# ups_unit.net
KiCad netlist of a schematic drawn in EAGLE
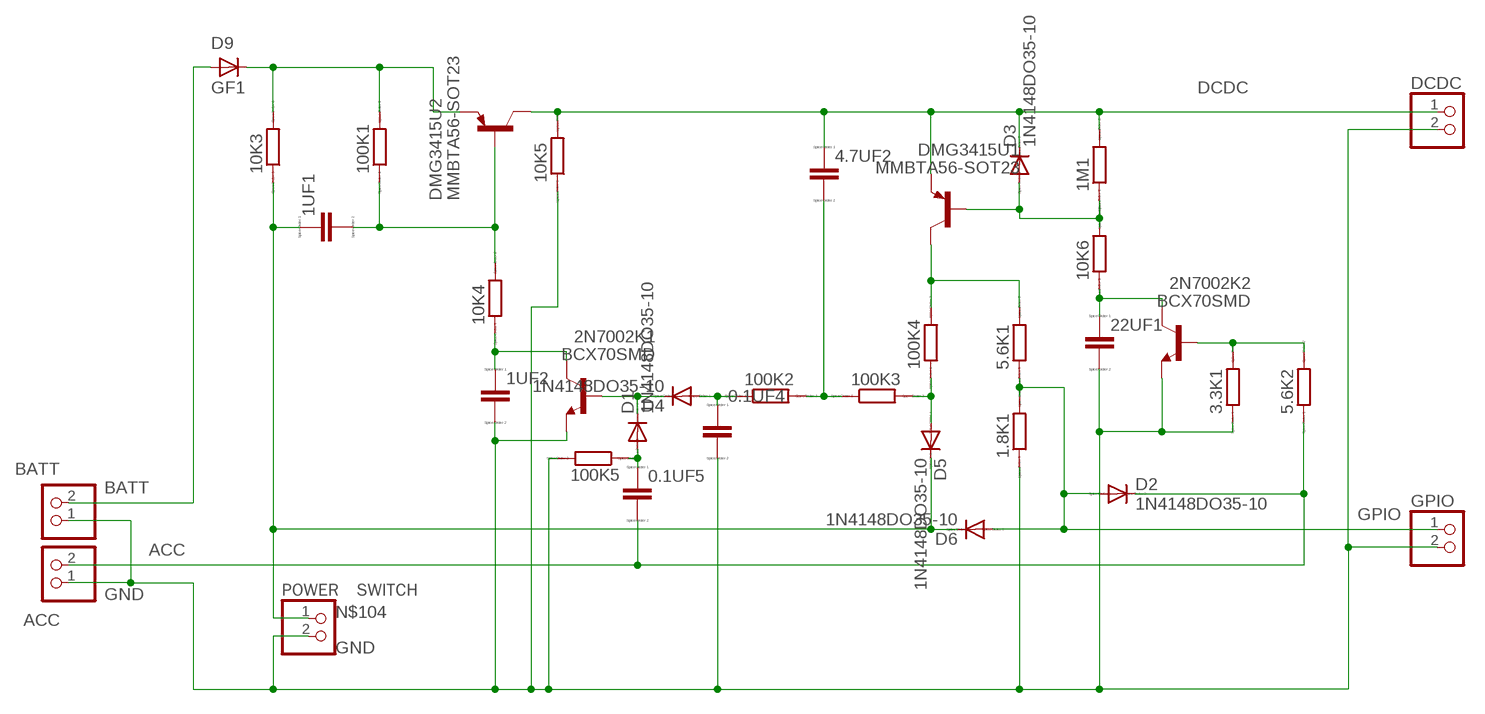
[diagram p0: schematic, sheet 1]

(export (version "E")
  (design (tool "Eeschema 10.0.6"))
  (components
    (comp (ref "0.1UF4")
      (value "CC1206")
      (footprint "eagle-import:C1206")
      (libsource (lib "eagle-import") (part "CC1206"))
    )
    (comp (ref "0.1UF5")
      (value "CC1206")
      (footprint "eagle-import:C1206")
      (libsource (lib "eagle-import") (part "CC1206"))
    )
    (comp (ref "1.8K1")
      (value "RR1206")
      (footprint "eagle-import:R1206")
      (libsource (lib "eagle-import") (part "RR1206"))
    )
    (comp (ref "1M1")
      (value "RR1206")
      (footprint "eagle-import:R1206")
      (libsource (lib "eagle-import") (part "RR1206"))
    )
    (comp (ref "1UF1")
      (value "CC0603")
      (footprint "eagle-import:C0603")
      (libsource (lib "eagle-import") (part "CC0603"))
    )
    (comp (ref "1UF2")
      (value "CC0603")
      (footprint "eagle-import:C0603")
      (libsource (lib "eagle-import") (part "CC0603"))
    )
    (comp (ref "2N7002K1")
      (value "BCX70SMD")
      (footprint "eagle-import:SOT23")
      (libsource (lib "eagle-import") (part "BCX70SMD"))
    )
    (comp (ref "2N7002K2")
      (value "BCX70SMD")
      (footprint "eagle-import:SOT23")
      (libsource (lib "eagle-import") (part "BCX70SMD"))
    )
    (comp (ref "3.3K1")
      (value "RR1206")
      (footprint "eagle-import:R1206")
      (libsource (lib "eagle-import") (part "RR1206"))
    )
    (comp (ref "4.7UF2")
      (value "CC2012")
      (footprint "eagle-import:C2012")
      (libsource (lib "eagle-import") (part "CC2012"))
    )
    (comp (ref "5.6K1")
      (value "RR1206")
      (footprint "eagle-import:R1206")
      (libsource (lib "eagle-import") (part "RR1206"))
    )
    (comp (ref "5.6K2")
      (value "RR1206")
      (footprint "eagle-import:R1206")
      (libsource (lib "eagle-import") (part "RR1206"))
    )
    (comp (ref "10K3")
      (value "RR1206")
      (footprint "eagle-import:R1206")
      (libsource (lib "eagle-import") (part "RR1206"))
    )
    (comp (ref "10K4")
      (value "RR1206")
      (footprint "eagle-import:R1206")
      (libsource (lib "eagle-import") (part "RR1206"))
    )
    (comp (ref "10K5")
      (value "RR1206")
      (footprint "eagle-import:R1206")
      (libsource (lib "eagle-import") (part "RR1206"))
    )
    (comp (ref "10K6")
      (value "RR1206")
      (footprint "eagle-import:R1206")
      (libsource (lib "eagle-import") (part "RR1206"))
    )
    (comp (ref "22UF1")
      (value "C")
      (footprint "eagle-import:C0805")
      (libsource (lib "eagle-import") (part "C"))
    )
    (comp (ref "100K1")
      (value "RR1206")
      (footprint "eagle-import:R1206")
      (libsource (lib "eagle-import") (part "RR1206"))
    )
    (comp (ref "100K2")
      (value "RR1206")
      (footprint "eagle-import:R1206")
      (libsource (lib "eagle-import") (part "RR1206"))
    )
    (comp (ref "100K3")
      (value "RR1206")
      (footprint "eagle-import:R1206")
      (libsource (lib "eagle-import") (part "RR1206"))
    )
    (comp (ref "100K4")
      (value "RR1206")
      (footprint "eagle-import:R1206")
      (libsource (lib "eagle-import") (part "RR1206"))
    )
    (comp (ref "100K5")
      (value "RR1206")
      (footprint "eagle-import:R1206")
      (libsource (lib "eagle-import") (part "RR1206"))
    )
    (comp (ref "ACC")
      (value "PINHD-1X2")
      (footprint "eagle-import:1X02")
      (libsource (lib "eagle-import") (part "PINHD-1X2"))
    )
    (comp (ref "BATT")
      (value "PINHD-1X2")
      (footprint "eagle-import:1X02")
      (libsource (lib "eagle-import") (part "PINHD-1X2"))
    )
    (comp (ref "D1")
      (value "1N4148DO35-10")
      (footprint "eagle-import:DO35-10")
      (libsource (lib "eagle-import") (part "1N4148DO35-10"))
    )
    (comp (ref "D2")
      (value "1N4148DO35-10")
      (footprint "eagle-import:DO35-10")
      (libsource (lib "eagle-import") (part "1N4148DO35-10"))
    )
    (comp (ref "D3")
      (value "1N4148DO35-10")
      (footprint "eagle-import:DO35-10")
      (libsource (lib "eagle-import") (part "1N4148DO35-10"))
    )
    (comp (ref "D4")
      (value "1N4148DO35-10")
      (footprint "eagle-import:DO35-10")
      (libsource (lib "eagle-import") (part "1N4148DO35-10"))
    )
    (comp (ref "D5")
      (value "1N4148DO35-10")
      (footprint "eagle-import:DO35-10")
      (libsource (lib "eagle-import") (part "1N4148DO35-10"))
    )
    (comp (ref "D6")
      (value "1N4148DO35-10")
      (footprint "eagle-import:DO35-10")
      (libsource (lib "eagle-import") (part "1N4148DO35-10"))
    )
    (comp (ref "D9")
      (value "GF1")
      (footprint "eagle-import:SMA-DO214AC")
      (libsource (lib "eagle-import") (part "GF1"))
    )
    (comp (ref "DCDC")
      (value "PINHD-1X2")
      (footprint "eagle-import:1X02")
      (libsource (lib "eagle-import") (part "PINHD-1X2"))
    )
    (comp (ref "DMG3415U1")
      (value "MMBTA56-SOT23")
      (footprint "eagle-import:SOT23")
      (libsource (lib "eagle-import") (part "-?SOT23MMBTA56"))
    )
    (comp (ref "DMG3415U2")
      (value "MMBTA56-SOT23")
      (footprint "eagle-import:SOT23")
      (libsource (lib "eagle-import") (part "-?SOT23MMBTA56"))
    )
    (comp (ref "GPIO")
      (value "PINHD-1X2")
      (footprint "eagle-import:1X02")
      (libsource (lib "eagle-import") (part "PINHD-1X2"))
    )
    (comp (ref "POWER　SWITCH")
      (value "PINHD-1X2")
      (footprint "eagle-import:1X02")
      (libsource (lib "eagle-import") (part "PINHD-1X2"))
    )
  )
  (nets
    (net (code "1") (name "/ACC") (class "Default")
      (node (ref "0.1UF5") (pin "2") (pinfunction "2_2") (pintype "passive"))
      (node (ref "5.6K2") (pin "1") (pinfunction "1_1") (pintype "passive"))
      (node (ref "ACC") (pin "2") (pinfunction "2_2") (pintype "passive"))
      (node (ref "D2") (pin "C") (pinfunction "C_C") (pintype "passive"))
    )
    (net (code "2") (name "/BATT") (class "Default")
      (node (ref "BATT") (pin "2") (pinfunction "2_2") (pintype "passive"))
      (node (ref "D9") (pin "A") (pinfunction "A_A") (pintype "passive"))
    )
    (net (code "3") (name "/DCDC") (class "Default")
      (node (ref "10K5") (pin "2") (pinfunction "2_2") (pintype "passive"))
      (node (ref "1M1") (pin "2") (pinfunction "2_2") (pintype "passive"))
      (node (ref "4.7UF2") (pin "1") (pinfunction "1_1") (pintype "passive"))
      (node (ref "D3") (pin "C") (pinfunction "C_C") (pintype "passive"))
      (node (ref "DCDC") (pin "1") (pinfunction "1_1") (pintype "passive"))
      (node (ref "DMG3415U1") (pin "2") (pinfunction "E_2") (pintype "passive"))
      (node (ref "DMG3415U2") (pin "3") (pinfunction "C_3") (pintype "passive"))
    )
    (net (code "4") (name "/GND") (class "Default")
      (node (ref "0.1UF4") (pin "2") (pinfunction "2_2") (pintype "passive"))
      (node (ref "1.8K1") (pin "1") (pinfunction "1_1") (pintype "passive"))
      (node (ref "100K5") (pin "2") (pinfunction "2_2") (pintype "passive"))
      (node (ref "10K5") (pin "1") (pinfunction "1_1") (pintype "passive"))
      (node (ref "1UF2") (pin "2") (pinfunction "2_2") (pintype "passive"))
      (node (ref "22UF1") (pin "2") (pinfunction "2_2") (pintype "passive"))
      (node (ref "2N7002K1") (pin "2") (pinfunction "E_2") (pintype "passive"))
      (node (ref "2N7002K2") (pin "2") (pinfunction "E_2") (pintype "passive"))
      (node (ref "3.3K1") (pin "1") (pinfunction "1_1") (pintype "passive"))
      (node (ref "ACC") (pin "1") (pinfunction "1_1") (pintype "passive"))
      (node (ref "BATT") (pin "1") (pinfunction "1_1") (pintype "passive"))
      (node (ref "DCDC") (pin "2") (pinfunction "2_2") (pintype "passive"))
      (node (ref "GPIO") (pin "2") (pinfunction "2_2") (pintype "passive"))
      (node (ref "POWER　SWITCH") (pin "2") (pinfunction "2_2") (pintype "passive"))
    )
    (net (code "5") (name "/GPIO") (class "Default")
      (node (ref "1.8K1") (pin "2") (pinfunction "2_2") (pintype "passive"))
      (node (ref "5.6K1") (pin "1") (pinfunction "1_1") (pintype "passive"))
      (node (ref "D2") (pin "A") (pinfunction "A_A") (pintype "passive"))
      (node (ref "D6") (pin "A") (pinfunction "A_A") (pintype "passive"))
      (node (ref "GPIO") (pin "1") (pinfunction "1_1") (pintype "passive"))
    )
    (net (code "6") (name "/N$104") (class "Default")
      (node (ref "10K3") (pin "1") (pinfunction "1_1") (pintype "passive"))
      (node (ref "1UF1") (pin "1") (pinfunction "1_1") (pintype "passive"))
      (node (ref "D5") (pin "C") (pinfunction "C_C") (pintype "passive"))
      (node (ref "D6") (pin "C") (pinfunction "C_C") (pintype "passive"))
      (node (ref "POWER　SWITCH") (pin "1") (pinfunction "1_1") (pintype "passive"))
    )
    (net (code "7") (name "Net-(0.1UF4-Pad1)") (class "Default")
      (node (ref "0.1UF4") (pin "1") (pinfunction "1_1") (pintype "passive"))
      (node (ref "100K2") (pin "1") (pinfunction "1_1") (pintype "passive"))
      (node (ref "D4") (pin "A") (pinfunction "A_A") (pintype "passive"))
    )
    (net (code "8") (name "Net-(0.1UF5-Pad1)") (class "Default")
      (node (ref "0.1UF5") (pin "1") (pinfunction "1_1") (pintype "passive"))
      (node (ref "100K5") (pin "1") (pinfunction "1_1") (pintype "passive"))
      (node (ref "D1") (pin "A") (pinfunction "A_A") (pintype "passive"))
    )
    (net (code "9") (name "Net-(2N7002K1-B)") (class "Default")
      (node (ref "2N7002K1") (pin "1") (pinfunction "B_1") (pintype "passive"))
      (node (ref "D1") (pin "C") (pinfunction "C_C") (pintype "passive"))
      (node (ref "D4") (pin "C") (pinfunction "C_C") (pintype "passive"))
    )
    (net (code "10") (name "Net-(2N7002K1-C)") (class "Default")
      (node (ref "10K4") (pin "1") (pinfunction "1_1") (pintype "passive"))
      (node (ref "1UF2") (pin "1") (pinfunction "1_1") (pintype "passive"))
      (node (ref "2N7002K1") (pin "3") (pinfunction "C_3") (pintype "passive"))
    )
    (net (code "11") (name "Net-(2N7002K2-B)") (class "Default")
      (node (ref "2N7002K2") (pin "1") (pinfunction "B_1") (pintype "passive"))
      (node (ref "3.3K1") (pin "2") (pinfunction "2_2") (pintype "passive"))
      (node (ref "5.6K2") (pin "2") (pinfunction "2_2") (pintype "passive"))
    )
    (net (code "12") (name "Net-(2N7002K2-C)") (class "Default")
      (node (ref "10K6") (pin "1") (pinfunction "1_1") (pintype "passive"))
      (node (ref "22UF1") (pin "1") (pinfunction "1_1") (pintype "passive"))
      (node (ref "2N7002K2") (pin "3") (pinfunction "C_3") (pintype "passive"))
    )
    (net (code "13") (name "Net-(100K2-Pad2)") (class "Default")
      (node (ref "100K2") (pin "2") (pinfunction "2_2") (pintype "passive"))
      (node (ref "100K3") (pin "1") (pinfunction "1_1") (pintype "passive"))
      (node (ref "4.7UF2") (pin "2") (pinfunction "2_2") (pintype "passive"))
    )
    (net (code "14") (name "Net-(100K3-Pad2)") (class "Default")
      (node (ref "100K3") (pin "2") (pinfunction "2_2") (pintype "passive"))
      (node (ref "100K4") (pin "1") (pinfunction "1_1") (pintype "passive"))
      (node (ref "D5") (pin "A") (pinfunction "A_A") (pintype "passive"))
    )
    (net (code "15") (name "Net-(D9-C)") (class "Default")
      (node (ref "100K1") (pin "2") (pinfunction "2_2") (pintype "passive"))
      (node (ref "10K3") (pin "2") (pinfunction "2_2") (pintype "passive"))
      (node (ref "D9") (pin "K") (pinfunction "C_K") (pintype "passive"))
      (node (ref "DMG3415U2") (pin "2") (pinfunction "E_2") (pintype "passive"))
    )
    (net (code "16") (name "Net-(DMG3415U1-B)") (class "Default")
      (node (ref "10K6") (pin "2") (pinfunction "2_2") (pintype "passive"))
      (node (ref "1M1") (pin "1") (pinfunction "1_1") (pintype "passive"))
      (node (ref "D3") (pin "A") (pinfunction "A_A") (pintype "passive"))
      (node (ref "DMG3415U1") (pin "1") (pinfunction "B_1") (pintype "passive"))
    )
    (net (code "17") (name "Net-(DMG3415U1-C)") (class "Default")
      (node (ref "100K4") (pin "2") (pinfunction "2_2") (pintype "passive"))
      (node (ref "5.6K1") (pin "2") (pinfunction "2_2") (pintype "passive"))
      (node (ref "DMG3415U1") (pin "3") (pinfunction "C_3") (pintype "passive"))
    )
    (net (code "18") (name "Net-(DMG3415U2-B)") (class "Default")
      (node (ref "100K1") (pin "1") (pinfunction "1_1") (pintype "passive"))
      (node (ref "10K4") (pin "2") (pinfunction "2_2") (pintype "passive"))
      (node (ref "1UF1") (pin "2") (pinfunction "2_2") (pintype "passive"))
      (node (ref "DMG3415U2") (pin "1") (pinfunction "B_1") (pintype "passive"))
    )
  )
)
